# control.net
KiCad netlist of a schematic drawn in EAGLE
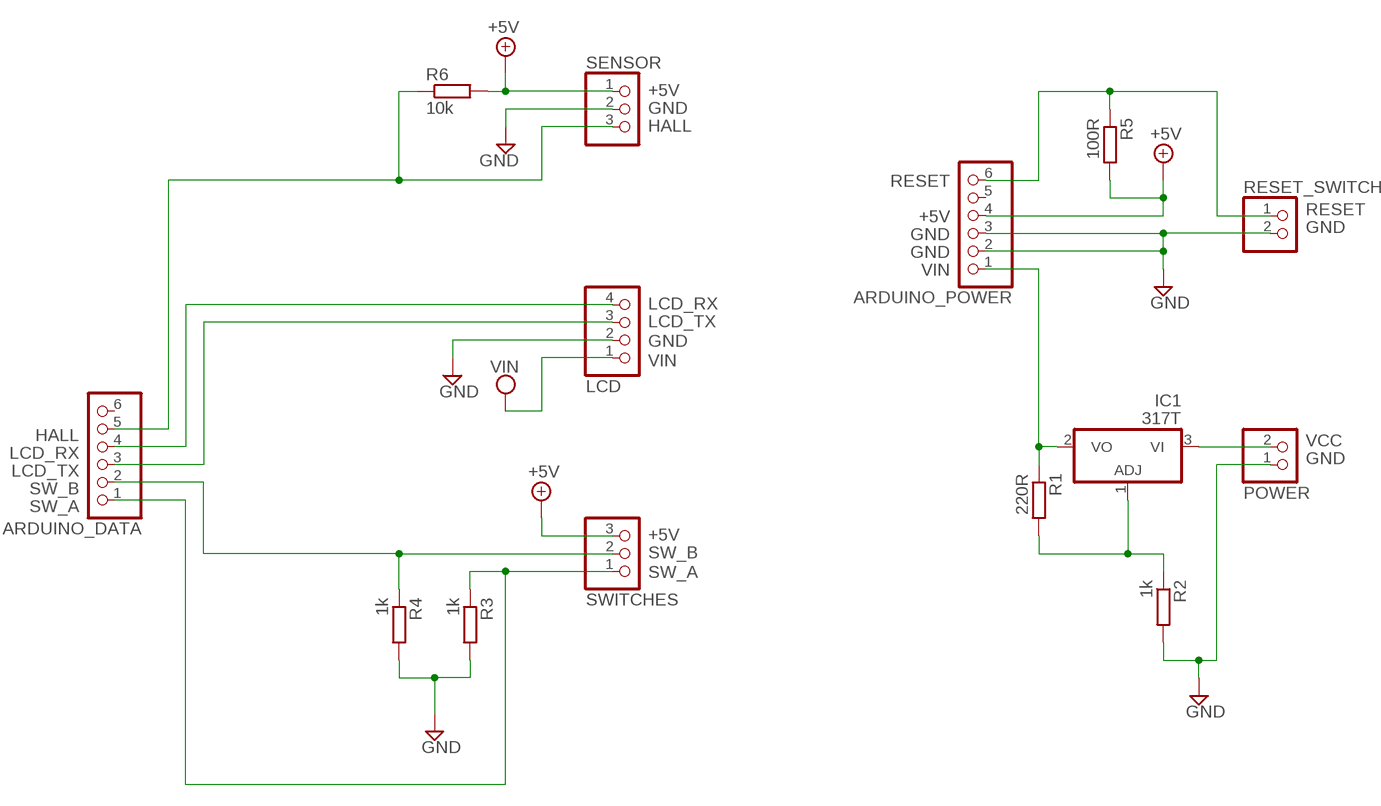
[diagram p0: schematic, sheet 1]

(export (version "E")
  (design (tool "Eeschema 10.0.6"))
  (components
    (comp (ref "ARDUINO_DATA")
      (value "PINHD-1X6")
      (footprint "eagle-import:1X06")
      (libsource (lib "eagle-import") (part "PINHD-1X6"))
    )
    (comp (ref "ARDUINO_POWER")
      (value "PINHD-1X6")
      (footprint "eagle-import:1X06")
      (libsource (lib "eagle-import") (part "PINHD-1X6"))
    )
    (comp (ref "IC1")
      (value "317T")
      (footprint "eagle-import:TO220H")
      (libsource (lib "eagle-import") (part "317T"))
    )
    (comp (ref "LCD")
      (value "PINHD-1X4")
      (footprint "eagle-import:1X04")
      (libsource (lib "eagle-import") (part "PINHD-1X4"))
    )
    (comp (ref "POWER")
      (value "PINHD-1X2")
      (footprint "eagle-import:1X02")
      (libsource (lib "eagle-import") (part "PINHD-1X2"))
    )
    (comp (ref "R1")
      (value "220R")
      (footprint "eagle-import:0204_7")
      (libsource (lib "eagle-import") (part "R-EU_0204/7"))
    )
    (comp (ref "R2")
      (value "1k")
      (footprint "eagle-import:0204_7")
      (libsource (lib "eagle-import") (part "R-EU_0204/7"))
    )
    (comp (ref "R3")
      (value "1k")
      (footprint "eagle-import:0207_10")
      (libsource (lib "eagle-import") (part "R-EU_0207/10"))
    )
    (comp (ref "R4")
      (value "1k")
      (footprint "eagle-import:0204_7")
      (libsource (lib "eagle-import") (part "R-EU_0204/7"))
    )
    (comp (ref "R5")
      (value "100R")
      (footprint "eagle-import:0204_7")
      (libsource (lib "eagle-import") (part "R-EU_0204/7"))
    )
    (comp (ref "R6")
      (value "10k")
      (footprint "eagle-import:0207_7")
      (libsource (lib "eagle-import") (part "R-EU_0207/7"))
    )
    (comp (ref "RESET_SWITCH")
      (value "PINHD-1X2")
      (footprint "eagle-import:1X02")
      (libsource (lib "eagle-import") (part "PINHD-1X2"))
    )
    (comp (ref "SENSOR")
      (value "PINHD-1X3")
      (footprint "eagle-import:1X03")
      (libsource (lib "eagle-import") (part "PINHD-1X3"))
    )
    (comp (ref "SWITCHES")
      (value "PINHD-1X3")
      (footprint "eagle-import:1X03")
      (libsource (lib "eagle-import") (part "PINHD-1X3"))
    )
  )
  (nets
    (net (code "1") (name "+5V") (class "Default")
      (node (ref "ARDUINO_POWER") (pin "4") (pinfunction "4_4") (pintype "passive"))
      (node (ref "R5") (pin "2") (pinfunction "2_2") (pintype "passive"))
      (node (ref "R6") (pin "2") (pinfunction "2_2") (pintype "passive"))
      (node (ref "SENSOR") (pin "1") (pinfunction "1_1") (pintype "passive"))
      (node (ref "SWITCHES") (pin "3") (pinfunction "3_3") (pintype "passive"))
    )
    (net (code "2") (name "/HALL") (class "Default")
      (node (ref "ARDUINO_DATA") (pin "5") (pinfunction "5_5") (pintype "passive"))
      (node (ref "R6") (pin "1") (pinfunction "1_1") (pintype "passive"))
      (node (ref "SENSOR") (pin "3") (pinfunction "3_3") (pintype "passive"))
    )
    (net (code "3") (name "/LCD_RX") (class "Default")
      (node (ref "ARDUINO_DATA") (pin "4") (pinfunction "4_4") (pintype "passive"))
      (node (ref "LCD") (pin "4") (pinfunction "4_4") (pintype "passive"))
    )
    (net (code "4") (name "/LCD_TX") (class "Default")
      (node (ref "ARDUINO_DATA") (pin "3") (pinfunction "3_3") (pintype "passive"))
      (node (ref "LCD") (pin "3") (pinfunction "3_3") (pintype "passive"))
    )
    (net (code "5") (name "/RESET") (class "Default")
      (node (ref "ARDUINO_POWER") (pin "6") (pinfunction "6_6") (pintype "passive"))
      (node (ref "R5") (pin "1") (pinfunction "1_1") (pintype "passive"))
      (node (ref "RESET_SWITCH") (pin "1") (pinfunction "1_1") (pintype "passive"))
    )
    (net (code "6") (name "/SW_A") (class "Default")
      (node (ref "ARDUINO_DATA") (pin "1") (pinfunction "1_1") (pintype "passive"))
      (node (ref "R3") (pin "1") (pinfunction "1_1") (pintype "passive"))
      (node (ref "SWITCHES") (pin "1") (pinfunction "1_1") (pintype "passive"))
    )
    (net (code "7") (name "/SW_B") (class "Default")
      (node (ref "ARDUINO_DATA") (pin "2") (pinfunction "2_2") (pintype "passive"))
      (node (ref "R4") (pin "1") (pinfunction "1_1") (pintype "passive"))
      (node (ref "SWITCHES") (pin "2") (pinfunction "2_2") (pintype "passive"))
    )
    (net (code "8") (name "/VCC") (class "Default")
      (node (ref "IC1") (pin "3") (pinfunction "VI_3") (pintype "input"))
      (node (ref "POWER") (pin "2") (pinfunction "2_2") (pintype "passive"))
    )
    (net (code "9") (name "GND") (class "Default")
      (node (ref "ARDUINO_POWER") (pin "2") (pinfunction "2_2") (pintype "passive"))
      (node (ref "ARDUINO_POWER") (pin "3") (pinfunction "3_3") (pintype "passive"))
      (node (ref "LCD") (pin "2") (pinfunction "2_2") (pintype "passive"))
      (node (ref "POWER") (pin "1") (pinfunction "1_1") (pintype "passive"))
      (node (ref "R2") (pin "2") (pinfunction "2_2") (pintype "passive"))
      (node (ref "R3") (pin "2") (pinfunction "2_2") (pintype "passive"))
      (node (ref "R4") (pin "2") (pinfunction "2_2") (pintype "passive"))
      (node (ref "RESET_SWITCH") (pin "2") (pinfunction "2_2") (pintype "passive"))
      (node (ref "SENSOR") (pin "2") (pinfunction "2_2") (pintype "passive"))
    )
    (net (code "10") (name "Net-(IC1-ADJ)") (class "Default")
      (node (ref "IC1") (pin "1") (pinfunction "ADJ_1") (pintype "input"))
      (node (ref "R1") (pin "2") (pinfunction "2_2") (pintype "passive"))
      (node (ref "R2") (pin "1") (pinfunction "1_1") (pintype "passive"))
    )
    (net (code "11") (name "VIN") (class "Default")
      (node (ref "ARDUINO_POWER") (pin "1") (pinfunction "1_1") (pintype "passive"))
      (node (ref "IC1") (pin "2") (pinfunction "VO_2") (pintype "passive"))
      (node (ref "LCD") (pin "1") (pinfunction "1_1") (pintype "passive"))
      (node (ref "R1") (pin "1") (pinfunction "1_1") (pintype "passive"))
    )
    (net (code "12") (name "unconnected-(ARDUINO_DATA-Pad6)") (class "Default")
      (node (ref "ARDUINO_DATA") (pin "6") (pinfunction "6_6") (pintype "passive"))
    )
    (net (code "13") (name "unconnected-(ARDUINO_POWER-Pad5)") (class "Default")
      (node (ref "ARDUINO_POWER") (pin "5") (pinfunction "5_5") (pintype "passive"))
    )
  )
)
